# powerBoard.net
KiCad netlist of a schematic drawn in EAGLE
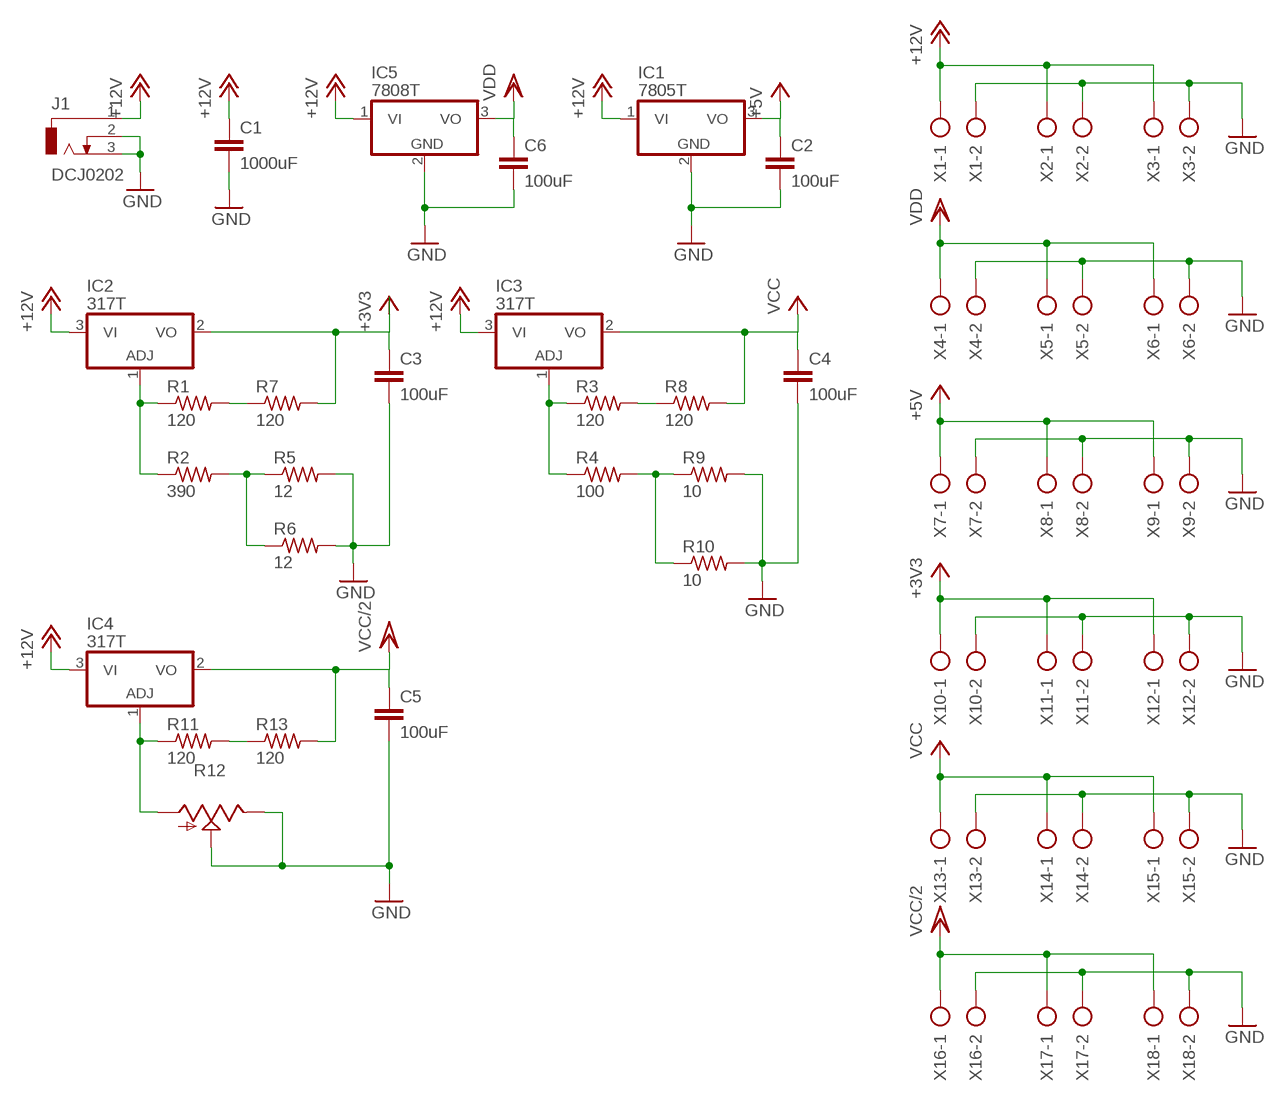
[diagram p0: schematic, sheet 1]

(export (version "E")
  (design (tool "Eeschema 10.0.6"))
  (components
    (comp (ref "C1")
      (value "1000uF")
      (footprint "eagle-import:C5B7.2")
      (libsource (lib "eagle-import") (part "C5/7.2"))
    )
    (comp (ref "C2")
      (value "100uF")
      (footprint "eagle-import:C5B7.2")
      (libsource (lib "eagle-import") (part "C5/7.2"))
    )
    (comp (ref "C3")
      (value "100uF")
      (footprint "eagle-import:C5B7.2")
      (libsource (lib "eagle-import") (part "C5/7.2"))
    )
    (comp (ref "C4")
      (value "100uF")
      (footprint "eagle-import:C5B7.2")
      (libsource (lib "eagle-import") (part "C5/7.2"))
    )
    (comp (ref "C5")
      (value "100uF")
      (footprint "eagle-import:C5B7.2")
      (libsource (lib "eagle-import") (part "C5/7.2"))
    )
    (comp (ref "C6")
      (value "100uF")
      (footprint "eagle-import:C5B7.2")
      (libsource (lib "eagle-import") (part "C5/7.2"))
    )
    (comp (ref "IC1")
      (value "7805T")
      (footprint "eagle-import:TO220H")
      (libsource (lib "eagle-import") (part "78T05"))
    )
    (comp (ref "IC2")
      (value "317T")
      (footprint "eagle-import:TO220H")
      (libsource (lib "eagle-import") (part "317T"))
    )
    (comp (ref "IC3")
      (value "317T")
      (footprint "eagle-import:TO220H")
      (libsource (lib "eagle-import") (part "317T"))
    )
    (comp (ref "IC4")
      (value "317T")
      (footprint "eagle-import:TO220H")
      (libsource (lib "eagle-import") (part "317T"))
    )
    (comp (ref "IC5")
      (value "7808T")
      (footprint "eagle-import:TO220H")
      (libsource (lib "eagle-import") (part "78T08"))
    )
    (comp (ref "J1")
      (value "DCJ0202")
      (footprint "eagle-import:DCJ0202")
      (libsource (lib "eagle-import") (part "DCJ0202"))
    )
    (comp (ref "R1")
      (value "120")
      (footprint "eagle-import:0207_10")
      (libsource (lib "eagle-import") (part "R-US_0207/10"))
    )
    (comp (ref "R2")
      (value "390")
      (footprint "eagle-import:0207_10")
      (libsource (lib "eagle-import") (part "R-US_0207/10"))
    )
    (comp (ref "R3")
      (value "120")
      (footprint "eagle-import:0207_10")
      (libsource (lib "eagle-import") (part "R-US_0207/10"))
    )
    (comp (ref "R4")
      (value "100")
      (footprint "eagle-import:0207_10")
      (libsource (lib "eagle-import") (part "R-US_0207/10"))
    )
    (comp (ref "R5")
      (value "12")
      (footprint "eagle-import:0207_10")
      (libsource (lib "eagle-import") (part "R-US_0207/10"))
    )
    (comp (ref "R6")
      (value "12")
      (footprint "eagle-import:0207_10")
      (libsource (lib "eagle-import") (part "R-US_0207/10"))
    )
    (comp (ref "R7")
      (value "120")
      (footprint "eagle-import:0207_10")
      (libsource (lib "eagle-import") (part "R-US_0207/10"))
    )
    (comp (ref "R8")
      (value "120")
      (footprint "eagle-import:0207_10")
      (libsource (lib "eagle-import") (part "R-US_0207/10"))
    )
    (comp (ref "R9")
      (value "10")
      (footprint "eagle-import:0207_10")
      (libsource (lib "eagle-import") (part "R-US_0207/10"))
    )
    (comp (ref "R10")
      (value "10")
      (footprint "eagle-import:0207_10")
      (libsource (lib "eagle-import") (part "R-US_0207/10"))
    )
    (comp (ref "R11")
      (value "120")
      (footprint "eagle-import:0207_10")
      (libsource (lib "eagle-import") (part "R-US_0207/10"))
    )
    (comp (ref "R12")
      (value "TRIM_US-RJ9W")
      (footprint "eagle-import:RJ9W")
      (libsource (lib "eagle-import") (part "TRIM_US-RJ9W"))
    )
    (comp (ref "R13")
      (value "120")
      (footprint "eagle-import:0207_10")
      (libsource (lib "eagle-import") (part "R-US_0207/10"))
    )
    (comp (ref "X1")
      (value "AK300/2")
      (footprint "eagle-import:AK300_2")
      (libsource (lib "eagle-import") (part "AK300/2"))
    )
    (comp (ref "X2")
      (value "AK300/2")
      (footprint "eagle-import:AK300_2")
      (libsource (lib "eagle-import") (part "AK300/2"))
    )
    (comp (ref "X3")
      (value "AK300/2")
      (footprint "eagle-import:AK300_2")
      (libsource (lib "eagle-import") (part "AK300/2"))
    )
    (comp (ref "X4")
      (value "AK300/2")
      (footprint "eagle-import:AK300_2")
      (libsource (lib "eagle-import") (part "AK300/2"))
    )
    (comp (ref "X5")
      (value "AK300/2")
      (footprint "eagle-import:AK300_2")
      (libsource (lib "eagle-import") (part "AK300/2"))
    )
    (comp (ref "X6")
      (value "AK300/2")
      (footprint "eagle-import:AK300_2")
      (libsource (lib "eagle-import") (part "AK300/2"))
    )
    (comp (ref "X7")
      (value "AK300/2")
      (footprint "eagle-import:AK300_2")
      (libsource (lib "eagle-import") (part "AK300/2"))
    )
    (comp (ref "X8")
      (value "AK300/2")
      (footprint "eagle-import:AK300_2")
      (libsource (lib "eagle-import") (part "AK300/2"))
    )
    (comp (ref "X9")
      (value "AK300/2")
      (footprint "eagle-import:AK300_2")
      (libsource (lib "eagle-import") (part "AK300/2"))
    )
    (comp (ref "X10")
      (value "AK300/2")
      (footprint "eagle-import:AK300_2")
      (libsource (lib "eagle-import") (part "AK300/2"))
    )
    (comp (ref "X11")
      (value "AK300/2")
      (footprint "eagle-import:AK300_2")
      (libsource (lib "eagle-import") (part "AK300/2"))
    )
    (comp (ref "X12")
      (value "AK300/2")
      (footprint "eagle-import:AK300_2")
      (libsource (lib "eagle-import") (part "AK300/2"))
    )
    (comp (ref "X13")
      (value "AK300/2")
      (footprint "eagle-import:AK300_2")
      (libsource (lib "eagle-import") (part "AK300/2"))
    )
    (comp (ref "X14")
      (value "AK300/2")
      (footprint "eagle-import:AK300_2")
      (libsource (lib "eagle-import") (part "AK300/2"))
    )
    (comp (ref "X15")
      (value "AK300/2")
      (footprint "eagle-import:AK300_2")
      (libsource (lib "eagle-import") (part "AK300/2"))
    )
    (comp (ref "X16")
      (value "AK300/2")
      (footprint "eagle-import:AK300_2")
      (libsource (lib "eagle-import") (part "AK300/2"))
    )
    (comp (ref "X17")
      (value "AK300/2")
      (footprint "eagle-import:AK300_2")
      (libsource (lib "eagle-import") (part "AK300/2"))
    )
    (comp (ref "X18")
      (value "AK300/2")
      (footprint "eagle-import:AK300_2")
      (libsource (lib "eagle-import") (part "AK300/2"))
    )
  )
  (nets
    (net (code "1") (name "+3V3") (class "Default")
      (node (ref "C3") (pin "1") (pinfunction "1_1") (pintype "passive"))
      (node (ref "IC2") (pin "2") (pinfunction "VO_2") (pintype "passive"))
      (node (ref "R7") (pin "2") (pinfunction "2_2") (pintype "passive"))
      (node (ref "X10") (pin "1") (pinfunction "KL_1") (pintype "passive"))
      (node (ref "X11") (pin "1") (pinfunction "KL_1") (pintype "passive"))
      (node (ref "X12") (pin "1") (pinfunction "KL_1") (pintype "passive"))
    )
    (net (code "2") (name "+5V") (class "Default")
      (node (ref "C2") (pin "1") (pinfunction "1_1") (pintype "passive"))
      (node (ref "IC1") (pin "3") (pinfunction "VO_3") (pintype "passive"))
      (node (ref "X7") (pin "1") (pinfunction "KL_1") (pintype "passive"))
      (node (ref "X8") (pin "1") (pinfunction "KL_1") (pintype "passive"))
      (node (ref "X9") (pin "1") (pinfunction "KL_1") (pintype "passive"))
    )
    (net (code "3") (name "+12V") (class "Default")
      (node (ref "C1") (pin "1") (pinfunction "1_1") (pintype "passive"))
      (node (ref "IC1") (pin "1") (pinfunction "VI_1") (pintype "input"))
      (node (ref "IC2") (pin "3") (pinfunction "VI_3") (pintype "input"))
      (node (ref "IC3") (pin "3") (pinfunction "VI_3") (pintype "input"))
      (node (ref "IC4") (pin "3") (pinfunction "VI_3") (pintype "input"))
      (node (ref "IC5") (pin "1") (pinfunction "VI_1") (pintype "input"))
      (node (ref "J1") (pin "1") (pinfunction "1_1") (pintype "passive"))
      (node (ref "X1") (pin "1") (pinfunction "KL_1") (pintype "passive"))
      (node (ref "X2") (pin "1") (pinfunction "KL_1") (pintype "passive"))
      (node (ref "X3") (pin "1") (pinfunction "KL_1") (pintype "passive"))
    )
    (net (code "4") (name "GND") (class "Default")
      (node (ref "C1") (pin "2") (pinfunction "2_2") (pintype "passive"))
      (node (ref "C2") (pin "2") (pinfunction "2_2") (pintype "passive"))
      (node (ref "C3") (pin "2") (pinfunction "2_2") (pintype "passive"))
      (node (ref "C4") (pin "2") (pinfunction "2_2") (pintype "passive"))
      (node (ref "C5") (pin "2") (pinfunction "2_2") (pintype "passive"))
      (node (ref "C6") (pin "2") (pinfunction "2_2") (pintype "passive"))
      (node (ref "IC1") (pin "2") (pinfunction "GND_2") (pintype "passive"))
      (node (ref "IC5") (pin "2") (pinfunction "GND_2") (pintype "passive"))
      (node (ref "J1") (pin "2") (pinfunction "2_2") (pintype "passive"))
      (node (ref "J1") (pin "3") (pinfunction "3_3") (pintype "passive"))
      (node (ref "R10") (pin "2") (pinfunction "2_2") (pintype "passive"))
      (node (ref "R12") (pin "E") (pinfunction "E_E") (pintype "passive"))
      (node (ref "R12") (pin "S") (pinfunction "S_S") (pintype "passive"))
      (node (ref "R5") (pin "2") (pinfunction "2_2") (pintype "passive"))
      (node (ref "R6") (pin "2") (pinfunction "2_2") (pintype "passive"))
      (node (ref "R9") (pin "2") (pinfunction "2_2") (pintype "passive"))
      (node (ref "X1") (pin "2") (pinfunction "KL_2") (pintype "passive"))
      (node (ref "X10") (pin "2") (pinfunction "KL_2") (pintype "passive"))
      (node (ref "X11") (pin "2") (pinfunction "KL_2") (pintype "passive"))
      (node (ref "X12") (pin "2") (pinfunction "KL_2") (pintype "passive"))
      (node (ref "X13") (pin "2") (pinfunction "KL_2") (pintype "passive"))
      (node (ref "X14") (pin "2") (pinfunction "KL_2") (pintype "passive"))
      (node (ref "X15") (pin "2") (pinfunction "KL_2") (pintype "passive"))
      (node (ref "X16") (pin "2") (pinfunction "KL_2") (pintype "passive"))
      (node (ref "X17") (pin "2") (pinfunction "KL_2") (pintype "passive"))
      (node (ref "X18") (pin "2") (pinfunction "KL_2") (pintype "passive"))
      (node (ref "X2") (pin "2") (pinfunction "KL_2") (pintype "passive"))
      (node (ref "X3") (pin "2") (pinfunction "KL_2") (pintype "passive"))
      (node (ref "X4") (pin "2") (pinfunction "KL_2") (pintype "passive"))
      (node (ref "X5") (pin "2") (pinfunction "KL_2") (pintype "passive"))
      (node (ref "X6") (pin "2") (pinfunction "KL_2") (pintype "passive"))
      (node (ref "X7") (pin "2") (pinfunction "KL_2") (pintype "passive"))
      (node (ref "X8") (pin "2") (pinfunction "KL_2") (pintype "passive"))
      (node (ref "X9") (pin "2") (pinfunction "KL_2") (pintype "passive"))
    )
    (net (code "5") (name "Net-(IC2-ADJ)") (class "Default")
      (node (ref "IC2") (pin "1") (pinfunction "ADJ_1") (pintype "input"))
      (node (ref "R1") (pin "1") (pinfunction "1_1") (pintype "passive"))
      (node (ref "R2") (pin "1") (pinfunction "1_1") (pintype "passive"))
    )
    (net (code "6") (name "Net-(IC3-ADJ)") (class "Default")
      (node (ref "IC3") (pin "1") (pinfunction "ADJ_1") (pintype "input"))
      (node (ref "R3") (pin "1") (pinfunction "1_1") (pintype "passive"))
      (node (ref "R4") (pin "1") (pinfunction "1_1") (pintype "passive"))
    )
    (net (code "7") (name "Net-(IC4-ADJ)") (class "Default")
      (node (ref "IC4") (pin "1") (pinfunction "ADJ_1") (pintype "input"))
      (node (ref "R11") (pin "1") (pinfunction "1_1") (pintype "passive"))
      (node (ref "R12") (pin "A") (pinfunction "A_A") (pintype "passive"))
    )
    (net (code "8") (name "Net-(R1-Pad2)") (class "Default")
      (node (ref "R1") (pin "2") (pinfunction "2_2") (pintype "passive"))
      (node (ref "R7") (pin "1") (pinfunction "1_1") (pintype "passive"))
    )
    (net (code "9") (name "Net-(R2-Pad2)") (class "Default")
      (node (ref "R2") (pin "2") (pinfunction "2_2") (pintype "passive"))
      (node (ref "R5") (pin "1") (pinfunction "1_1") (pintype "passive"))
      (node (ref "R6") (pin "1") (pinfunction "1_1") (pintype "passive"))
    )
    (net (code "10") (name "Net-(R3-Pad2)") (class "Default")
      (node (ref "R3") (pin "2") (pinfunction "2_2") (pintype "passive"))
      (node (ref "R8") (pin "1") (pinfunction "1_1") (pintype "passive"))
    )
    (net (code "11") (name "Net-(R10-Pad1)") (class "Default")
      (node (ref "R10") (pin "1") (pinfunction "1_1") (pintype "passive"))
      (node (ref "R4") (pin "2") (pinfunction "2_2") (pintype "passive"))
      (node (ref "R9") (pin "1") (pinfunction "1_1") (pintype "passive"))
    )
    (net (code "12") (name "Net-(R11-Pad2)") (class "Default")
      (node (ref "R11") (pin "2") (pinfunction "2_2") (pintype "passive"))
      (node (ref "R13") (pin "1") (pinfunction "1_1") (pintype "passive"))
    )
    (net (code "13") (name "VCC") (class "Default")
      (node (ref "C4") (pin "1") (pinfunction "1_1") (pintype "passive"))
      (node (ref "IC3") (pin "2") (pinfunction "VO_2") (pintype "passive"))
      (node (ref "R8") (pin "2") (pinfunction "2_2") (pintype "passive"))
      (node (ref "X13") (pin "1") (pinfunction "KL_1") (pintype "passive"))
      (node (ref "X14") (pin "1") (pinfunction "KL_1") (pintype "passive"))
      (node (ref "X15") (pin "1") (pinfunction "KL_1") (pintype "passive"))
    )
    (net (code "14") (name "VCC{slash}2") (class "Default")
      (node (ref "C5") (pin "1") (pinfunction "1_1") (pintype "passive"))
      (node (ref "IC4") (pin "2") (pinfunction "VO_2") (pintype "passive"))
      (node (ref "R13") (pin "2") (pinfunction "2_2") (pintype "passive"))
      (node (ref "X16") (pin "1") (pinfunction "KL_1") (pintype "passive"))
      (node (ref "X17") (pin "1") (pinfunction "KL_1") (pintype "passive"))
      (node (ref "X18") (pin "1") (pinfunction "KL_1") (pintype "passive"))
    )
    (net (code "15") (name "VDD") (class "Default")
      (node (ref "C6") (pin "1") (pinfunction "1_1") (pintype "passive"))
      (node (ref "IC5") (pin "3") (pinfunction "VO_3") (pintype "passive"))
      (node (ref "X4") (pin "1") (pinfunction "KL_1") (pintype "passive"))
      (node (ref "X5") (pin "1") (pinfunction "KL_1") (pintype "passive"))
      (node (ref "X6") (pin "1") (pinfunction "KL_1") (pintype "passive"))
    )
  )
)
